# LM339rev3.net
KiCad netlist of a schematic drawn in EAGLE
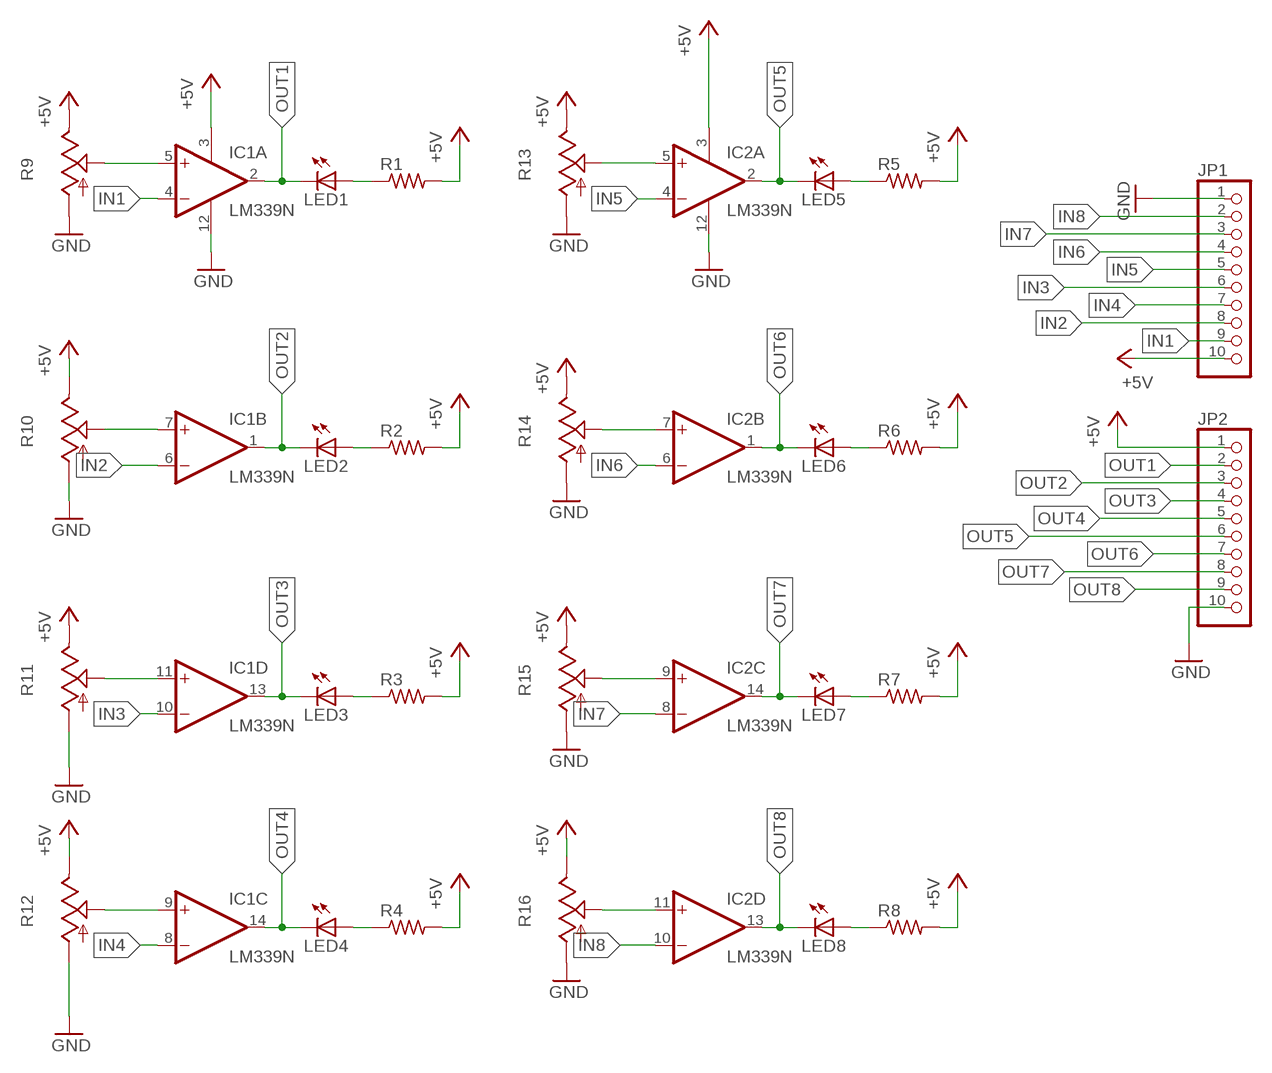
[diagram p0: schematic, sheet 1]

(export (version "E")
  (design (tool "Eeschema 10.0.6"))
  (components
    (comp (ref "IC1")
      (value "LM339N")
      (footprint "eagle-import:DIL14")
      (libsource (lib "eagle-import") (part "LM339N"))
    )
    (comp (ref "IC2")
      (value "LM339N")
      (footprint "eagle-import:DIL14")
      (libsource (lib "eagle-import") (part "LM339N"))
    )
    (comp (ref "JP1")
      (value "PINHD-1X10")
      (footprint "eagle-import:1X10")
      (libsource (lib "eagle-import") (part "PINHD-1X10"))
    )
    (comp (ref "JP2")
      (value "PINHD-1X10")
      (footprint "eagle-import:1X10")
      (libsource (lib "eagle-import") (part "PINHD-1X10"))
    )
    (comp (ref "LED1")
      (value "LED5MM")
      (footprint "eagle-import:LED5MM")
      (libsource (lib "eagle-import") (part "LED5MM"))
    )
    (comp (ref "LED2")
      (value "LED5MM")
      (footprint "eagle-import:LED5MM")
      (libsource (lib "eagle-import") (part "LED5MM"))
    )
    (comp (ref "LED3")
      (value "LED5MM")
      (footprint "eagle-import:LED5MM")
      (libsource (lib "eagle-import") (part "LED5MM"))
    )
    (comp (ref "LED4")
      (value "LED5MM")
      (footprint "eagle-import:LED5MM")
      (libsource (lib "eagle-import") (part "LED5MM"))
    )
    (comp (ref "LED5")
      (value "LED5MM")
      (footprint "eagle-import:LED5MM")
      (libsource (lib "eagle-import") (part "LED5MM"))
    )
    (comp (ref "LED6")
      (value "LED5MM")
      (footprint "eagle-import:LED5MM")
      (libsource (lib "eagle-import") (part "LED5MM"))
    )
    (comp (ref "LED7")
      (value "LED5MM")
      (footprint "eagle-import:LED5MM")
      (libsource (lib "eagle-import") (part "LED5MM"))
    )
    (comp (ref "LED8")
      (value "LED5MM")
      (footprint "eagle-import:LED5MM")
      (libsource (lib "eagle-import") (part "LED5MM"))
    )
    (comp (ref "R1")
      (value "R-US_0204/7")
      (footprint "eagle-import:0204_7")
      (libsource (lib "eagle-import") (part "R-US_0204/7"))
    )
    (comp (ref "R2")
      (value "R-US_0207/10")
      (footprint "eagle-import:0207_10")
      (libsource (lib "eagle-import") (part "R-US_0207/10"))
    )
    (comp (ref "R3")
      (value "R-US_0204/7")
      (footprint "eagle-import:0204_7")
      (libsource (lib "eagle-import") (part "R-US_0204/7"))
    )
    (comp (ref "R4")
      (value "R-US_0204/7")
      (footprint "eagle-import:0204_7")
      (libsource (lib "eagle-import") (part "R-US_0204/7"))
    )
    (comp (ref "R5")
      (value "R-US_0204/7")
      (footprint "eagle-import:0204_7")
      (libsource (lib "eagle-import") (part "R-US_0204/7"))
    )
    (comp (ref "R6")
      (value "R-US_0204/7")
      (footprint "eagle-import:0204_7")
      (libsource (lib "eagle-import") (part "R-US_0204/7"))
    )
    (comp (ref "R7")
      (value "R-US_0207/10")
      (footprint "eagle-import:0207_10")
      (libsource (lib "eagle-import") (part "R-US_0207/10"))
    )
    (comp (ref "R8")
      (value "R-US_0204/7")
      (footprint "eagle-import:0204_7")
      (libsource (lib "eagle-import") (part "R-US_0204/7"))
    )
    (comp (ref "R9")
      (value "TRIM_US-CA6V")
      (footprint "eagle-import:CA6V")
      (libsource (lib "eagle-import") (part "TRIM_US-CA6V"))
    )
    (comp (ref "R10")
      (value "TRIM_US-CA6V")
      (footprint "eagle-import:CA6V")
      (libsource (lib "eagle-import") (part "TRIM_US-CA6V"))
    )
    (comp (ref "R11")
      (value "TRIM_US-CA6V")
      (footprint "eagle-import:CA6V")
      (libsource (lib "eagle-import") (part "TRIM_US-CA6V"))
    )
    (comp (ref "R12")
      (value "TRIM_US-CA6V")
      (footprint "eagle-import:CA6V")
      (libsource (lib "eagle-import") (part "TRIM_US-CA6V"))
    )
    (comp (ref "R13")
      (value "TRIM_US-CA6V")
      (footprint "eagle-import:CA6V")
      (libsource (lib "eagle-import") (part "TRIM_US-CA6V"))
    )
    (comp (ref "R14")
      (value "TRIM_US-CA6V")
      (footprint "eagle-import:CA6V")
      (libsource (lib "eagle-import") (part "TRIM_US-CA6V"))
    )
    (comp (ref "R15")
      (value "TRIM_US-CA6V")
      (footprint "eagle-import:CA6V")
      (libsource (lib "eagle-import") (part "TRIM_US-CA6V"))
    )
    (comp (ref "R16")
      (value "TRIM_US-CA6V")
      (footprint "eagle-import:CA6V")
      (libsource (lib "eagle-import") (part "TRIM_US-CA6V"))
    )
  )
  (nets
    (net (code "1") (name "+5V") (class "Default")
      (node (ref "IC1") (pin "3") (pinfunction "V+_3") (pintype "power_in"))
      (node (ref "IC2") (pin "3") (pinfunction "V+_3") (pintype "power_in"))
      (node (ref "JP1") (pin "10") (pinfunction "10_10") (pintype "passive"))
      (node (ref "JP2") (pin "1") (pinfunction "1_1") (pintype "passive"))
      (node (ref "R1") (pin "2") (pinfunction "2_2") (pintype "passive"))
      (node (ref "R10") (pin "E") (pinfunction "E_E") (pintype "passive"))
      (node (ref "R11") (pin "E") (pinfunction "E_E") (pintype "passive"))
      (node (ref "R12") (pin "E") (pinfunction "E_E") (pintype "passive"))
      (node (ref "R13") (pin "E") (pinfunction "E_E") (pintype "passive"))
      (node (ref "R14") (pin "E") (pinfunction "E_E") (pintype "passive"))
      (node (ref "R15") (pin "E") (pinfunction "E_E") (pintype "passive"))
      (node (ref "R16") (pin "E") (pinfunction "E_E") (pintype "passive"))
      (node (ref "R2") (pin "2") (pinfunction "2_2") (pintype "passive"))
      (node (ref "R3") (pin "2") (pinfunction "2_2") (pintype "passive"))
      (node (ref "R4") (pin "2") (pinfunction "2_2") (pintype "passive"))
      (node (ref "R5") (pin "2") (pinfunction "2_2") (pintype "passive"))
      (node (ref "R6") (pin "2") (pinfunction "2_2") (pintype "passive"))
      (node (ref "R7") (pin "2") (pinfunction "2_2") (pintype "passive"))
      (node (ref "R8") (pin "2") (pinfunction "2_2") (pintype "passive"))
      (node (ref "R9") (pin "E") (pinfunction "E_E") (pintype "passive"))
    )
    (net (code "2") (name "GND") (class "Default")
      (node (ref "IC1") (pin "12") (pinfunction "GND_12") (pintype "power_in"))
      (node (ref "IC2") (pin "12") (pinfunction "GND_12") (pintype "power_in"))
      (node (ref "JP1") (pin "1") (pinfunction "1_1") (pintype "passive"))
      (node (ref "JP2") (pin "10") (pinfunction "10_10") (pintype "passive"))
      (node (ref "R10") (pin "A") (pinfunction "A_A") (pintype "passive"))
      (node (ref "R11") (pin "A") (pinfunction "A_A") (pintype "passive"))
      (node (ref "R12") (pin "A") (pinfunction "A_A") (pintype "passive"))
      (node (ref "R13") (pin "A") (pinfunction "A_A") (pintype "passive"))
      (node (ref "R14") (pin "A") (pinfunction "A_A") (pintype "passive"))
      (node (ref "R15") (pin "A") (pinfunction "A_A") (pintype "passive"))
      (node (ref "R16") (pin "A") (pinfunction "A_A") (pintype "passive"))
      (node (ref "R9") (pin "A") (pinfunction "A_A") (pintype "passive"))
    )
    (net (code "3") (name "IN1") (class "Default")
      (node (ref "IC1") (pin "4") (pinfunction "-IN_4") (pintype "input"))
      (node (ref "JP1") (pin "9") (pinfunction "9_9") (pintype "passive"))
    )
    (net (code "4") (name "IN2") (class "Default")
      (node (ref "IC1") (pin "6") (pinfunction "-IN_6") (pintype "input"))
      (node (ref "JP1") (pin "8") (pinfunction "8_8") (pintype "passive"))
    )
    (net (code "5") (name "IN3") (class "Default")
      (node (ref "IC1") (pin "10") (pinfunction "-IN_10") (pintype "input"))
      (node (ref "JP1") (pin "6") (pinfunction "6_6") (pintype "passive"))
    )
    (net (code "6") (name "IN4") (class "Default")
      (node (ref "IC1") (pin "8") (pinfunction "-IN_8") (pintype "input"))
      (node (ref "JP1") (pin "7") (pinfunction "7_7") (pintype "passive"))
    )
    (net (code "7") (name "IN5") (class "Default")
      (node (ref "IC2") (pin "4") (pinfunction "-IN_4") (pintype "input"))
      (node (ref "JP1") (pin "5") (pinfunction "5_5") (pintype "passive"))
    )
    (net (code "8") (name "IN6") (class "Default")
      (node (ref "IC2") (pin "6") (pinfunction "-IN_6") (pintype "input"))
      (node (ref "JP1") (pin "4") (pinfunction "4_4") (pintype "passive"))
    )
    (net (code "9") (name "IN7") (class "Default")
      (node (ref "IC2") (pin "8") (pinfunction "-IN_8") (pintype "input"))
      (node (ref "JP1") (pin "3") (pinfunction "3_3") (pintype "passive"))
    )
    (net (code "10") (name "IN8") (class "Default")
      (node (ref "IC2") (pin "10") (pinfunction "-IN_10") (pintype "input"))
      (node (ref "JP1") (pin "2") (pinfunction "2_2") (pintype "passive"))
    )
    (net (code "11") (name "Net-(IC1A-+IN)") (class "Default")
      (node (ref "IC1") (pin "5") (pinfunction "+IN_5") (pintype "input"))
      (node (ref "R9") (pin "S") (pinfunction "S_S") (pintype "passive"))
    )
    (net (code "12") (name "Net-(IC1B-+IN)") (class "Default")
      (node (ref "IC1") (pin "7") (pinfunction "+IN_7") (pintype "input"))
      (node (ref "R10") (pin "S") (pinfunction "S_S") (pintype "passive"))
    )
    (net (code "13") (name "Net-(IC1C-+IN)") (class "Default")
      (node (ref "IC1") (pin "9") (pinfunction "+IN_9") (pintype "input"))
      (node (ref "R12") (pin "S") (pinfunction "S_S") (pintype "passive"))
    )
    (net (code "14") (name "Net-(IC1D-+IN)") (class "Default")
      (node (ref "IC1") (pin "11") (pinfunction "+IN_11") (pintype "input"))
      (node (ref "R11") (pin "S") (pinfunction "S_S") (pintype "passive"))
    )
    (net (code "15") (name "Net-(IC2A-+IN)") (class "Default")
      (node (ref "IC2") (pin "5") (pinfunction "+IN_5") (pintype "input"))
      (node (ref "R13") (pin "S") (pinfunction "S_S") (pintype "passive"))
    )
    (net (code "16") (name "Net-(IC2B-+IN)") (class "Default")
      (node (ref "IC2") (pin "7") (pinfunction "+IN_7") (pintype "input"))
      (node (ref "R14") (pin "S") (pinfunction "S_S") (pintype "passive"))
    )
    (net (code "17") (name "Net-(IC2C-+IN)") (class "Default")
      (node (ref "IC2") (pin "9") (pinfunction "+IN_9") (pintype "input"))
      (node (ref "R15") (pin "S") (pinfunction "S_S") (pintype "passive"))
    )
    (net (code "18") (name "Net-(IC2D-+IN)") (class "Default")
      (node (ref "IC2") (pin "11") (pinfunction "+IN_11") (pintype "input"))
      (node (ref "R16") (pin "S") (pinfunction "S_S") (pintype "passive"))
    )
    (net (code "19") (name "Net-(LED1-PadA)") (class "Default")
      (node (ref "LED1") (pin "A") (pinfunction "A_A") (pintype "passive"))
      (node (ref "R1") (pin "1") (pinfunction "1_1") (pintype "passive"))
    )
    (net (code "20") (name "Net-(LED2-PadA)") (class "Default")
      (node (ref "LED2") (pin "A") (pinfunction "A_A") (pintype "passive"))
      (node (ref "R2") (pin "1") (pinfunction "1_1") (pintype "passive"))
    )
    (net (code "21") (name "Net-(LED3-PadA)") (class "Default")
      (node (ref "LED3") (pin "A") (pinfunction "A_A") (pintype "passive"))
      (node (ref "R3") (pin "1") (pinfunction "1_1") (pintype "passive"))
    )
    (net (code "22") (name "Net-(LED4-PadA)") (class "Default")
      (node (ref "LED4") (pin "A") (pinfunction "A_A") (pintype "passive"))
      (node (ref "R4") (pin "1") (pinfunction "1_1") (pintype "passive"))
    )
    (net (code "23") (name "Net-(LED5-PadA)") (class "Default")
      (node (ref "LED5") (pin "A") (pinfunction "A_A") (pintype "passive"))
      (node (ref "R5") (pin "1") (pinfunction "1_1") (pintype "passive"))
    )
    (net (code "24") (name "Net-(LED6-PadA)") (class "Default")
      (node (ref "LED6") (pin "A") (pinfunction "A_A") (pintype "passive"))
      (node (ref "R6") (pin "1") (pinfunction "1_1") (pintype "passive"))
    )
    (net (code "25") (name "Net-(LED7-PadA)") (class "Default")
      (node (ref "LED7") (pin "A") (pinfunction "A_A") (pintype "passive"))
      (node (ref "R7") (pin "1") (pinfunction "1_1") (pintype "passive"))
    )
    (net (code "26") (name "Net-(LED8-PadA)") (class "Default")
      (node (ref "LED8") (pin "A") (pinfunction "A_A") (pintype "passive"))
      (node (ref "R8") (pin "1") (pinfunction "1_1") (pintype "passive"))
    )
    (net (code "27") (name "OUT1") (class "Default")
      (node (ref "IC1") (pin "2") (pinfunction "OUT_2") (pintype "open_collector"))
      (node (ref "JP2") (pin "2") (pinfunction "2_2") (pintype "passive"))
      (node (ref "LED1") (pin "K") (pinfunction "C_K") (pintype "passive"))
    )
    (net (code "28") (name "OUT2") (class "Default")
      (node (ref "IC1") (pin "1") (pinfunction "OUT_1") (pintype "open_collector"))
      (node (ref "JP2") (pin "3") (pinfunction "3_3") (pintype "passive"))
      (node (ref "LED2") (pin "K") (pinfunction "C_K") (pintype "passive"))
    )
    (net (code "29") (name "OUT3") (class "Default")
      (node (ref "IC1") (pin "13") (pinfunction "OUT_13") (pintype "open_collector"))
      (node (ref "JP2") (pin "4") (pinfunction "4_4") (pintype "passive"))
      (node (ref "LED3") (pin "K") (pinfunction "C_K") (pintype "passive"))
    )
    (net (code "30") (name "OUT4") (class "Default")
      (node (ref "IC1") (pin "14") (pinfunction "OUT_14") (pintype "open_collector"))
      (node (ref "JP2") (pin "5") (pinfunction "5_5") (pintype "passive"))
      (node (ref "LED4") (pin "K") (pinfunction "C_K") (pintype "passive"))
    )
    (net (code "31") (name "OUT5") (class "Default")
      (node (ref "IC2") (pin "2") (pinfunction "OUT_2") (pintype "open_collector"))
      (node (ref "JP2") (pin "6") (pinfunction "6_6") (pintype "passive"))
      (node (ref "LED5") (pin "K") (pinfunction "C_K") (pintype "passive"))
    )
    (net (code "32") (name "OUT6") (class "Default")
      (node (ref "IC2") (pin "1") (pinfunction "OUT_1") (pintype "open_collector"))
      (node (ref "JP2") (pin "7") (pinfunction "7_7") (pintype "passive"))
      (node (ref "LED6") (pin "K") (pinfunction "C_K") (pintype "passive"))
    )
    (net (code "33") (name "OUT7") (class "Default")
      (node (ref "IC2") (pin "14") (pinfunction "OUT_14") (pintype "open_collector"))
      (node (ref "JP2") (pin "8") (pinfunction "8_8") (pintype "passive"))
      (node (ref "LED7") (pin "K") (pinfunction "C_K") (pintype "passive"))
    )
    (net (code "34") (name "OUT8") (class "Default")
      (node (ref "IC2") (pin "13") (pinfunction "OUT_13") (pintype "open_collector"))
      (node (ref "JP2") (pin "9") (pinfunction "9_9") (pintype "passive"))
      (node (ref "LED8") (pin "K") (pinfunction "C_K") (pintype "passive"))
    )
  )
)
